# VREG_RT9166-18PVL.net
KiCad netlist of a schematic drawn in Altium Designer
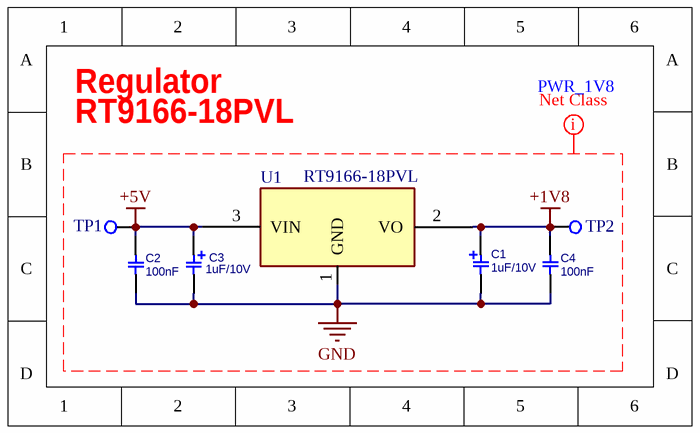
[diagram p0: VREG RT9166-18PVL.SchDoc]

(export (version "E")
  (design (tool "Eeschema 10.0.6"))
  (components
    (comp (ref "C1")
      (value "1uF/10V")
      (footprint "C_TN_3216")
      (description "CAP, SMD, TAN")
      (libsource (lib "Passive") (part "CAP_SMD_TAN"))
    )
    (comp (ref "C2")
      (value "100nF")
      (footprint "C0603S")
      (description "CAP, SMD, MLCC")
      (fields (field (name "MANF_P#") "MANF_PART#") (field (name "MANF") "Murata"))
      (libsource (lib "Passive") (part "CAP_SMD_MLCC"))
    )
    (comp (ref "C3")
      (value "1uF/10V")
      (footprint "C_TN_3216")
      (description "CAP, SMD, TAN")
      (libsource (lib "Passive") (part "CAP_SMD_TAN"))
    )
    (comp (ref "C4")
      (value "100nF")
      (footprint "C0603S")
      (description "CAP, SMD, MLCC")
      (fields (field (name "MANF_P#") "MANF_PART#") (field (name "MANF") "Murata"))
      (libsource (lib "Passive") (part "CAP_SMD_MLCC"))
    )
    (comp (ref "TP1")
      (value "Test Point")
      (footprint "TPSMD_C1")
      (libsource (lib "Passives") (part "Test Point"))
    )
    (comp (ref "TP2")
      (value "Test Point")
      (footprint "TPSMD_C1")
      (libsource (lib "Passives") (part "Test Point"))
    )
    (comp (ref "U1")
      (value "RT9166-18PVL")
      (footprint "SOT23_3")
      (description "REG, Linear, Fixed, 1.8v, 0.3A/0.6A, SOT23")
      (fields (field (name "MANF") "TI"))
      (libsource (lib "PW Components 97_472") (part "VREG_RT9166A-18PVL_SOT23"))
    )
  )
  (nets
    (net (code "1") (name "+1V8") (class "Default")
      (node (ref "C1") (pin "1") (pinfunction "1_1") (pintype "passive"))
      (node (ref "C4") (pin "1") (pinfunction "1_1") (pintype "passive"))
      (node (ref "TP2") (pin "1") (pinfunction "TP_1") (pintype "passive"))
      (node (ref "U1") (pin "2") (pinfunction "VO_2") (pintype "passive"))
    )
    (net (code "2") (name "+5V") (class "Default")
      (node (ref "C2") (pin "1") (pinfunction "1_1") (pintype "passive"))
      (node (ref "C3") (pin "1") (pinfunction "1_1") (pintype "passive"))
      (node (ref "TP1") (pin "1") (pinfunction "TP_1") (pintype "passive"))
      (node (ref "U1") (pin "3") (pinfunction "VIN_3") (pintype "passive"))
    )
    (net (code "3") (name "GND") (class "Default")
      (node (ref "C1") (pin "2") (pinfunction "2_2") (pintype "passive"))
      (node (ref "C2") (pin "2") (pinfunction "2_2") (pintype "passive"))
      (node (ref "C3") (pin "2") (pinfunction "2_2") (pintype "passive"))
      (node (ref "C4") (pin "2") (pinfunction "2_2") (pintype "passive"))
      (node (ref "U1") (pin "1") (pinfunction "GND_1") (pintype "passive"))
    )
  )
)
